# FireFly_AB.net
KiCad netlist of a schematic drawn in Altium Designer
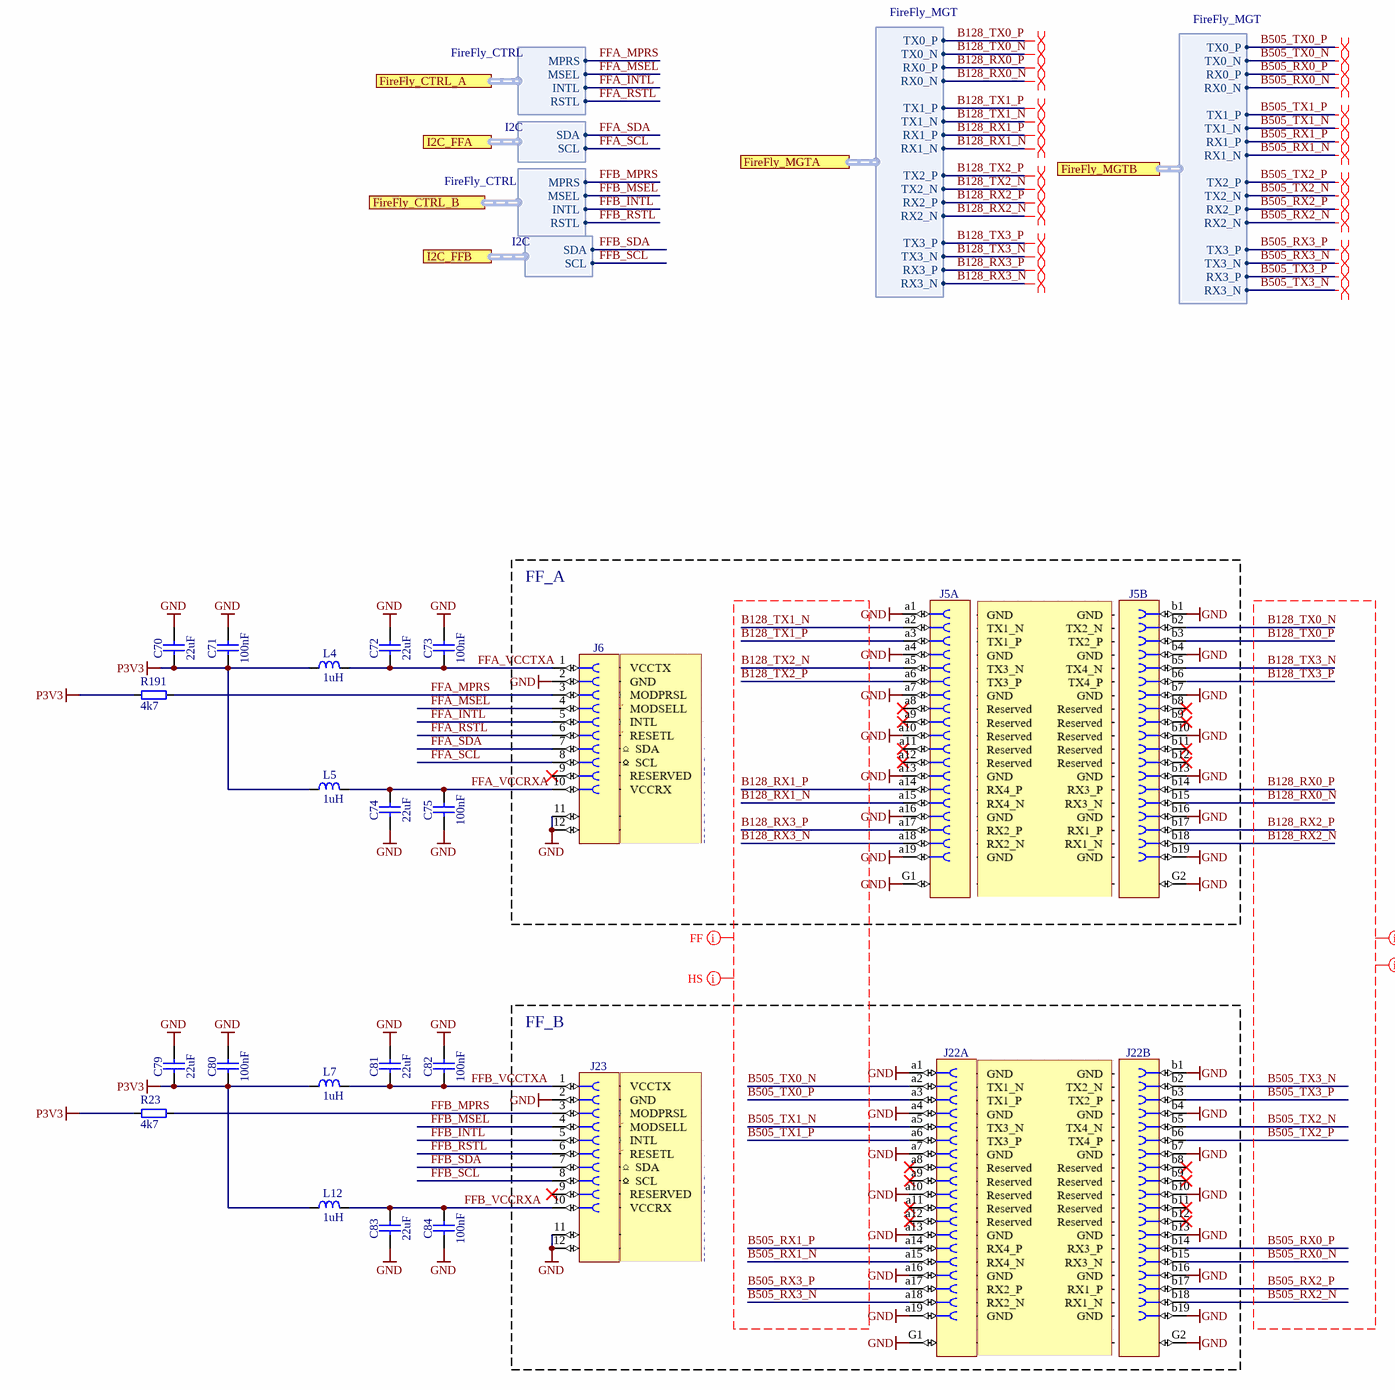
[diagram p0: FireFly_AB.SchDoc]

(export (version "E")
  (design (tool "Eeschema 10.0.6"))
  (components
    (comp (ref "C70")
      (value "22uF")
      (footprint "CAPC2012X135N")
      (description "Non-polarised capacitor")
      (fields
        (field (name "PART NUMBER") "CC0805_22UF_16V_10%_X5R")
        (field (name "VOLTAGE") "16V")
        (field (name "AUTHOR") "CERN DEM JLC")
      )
      (libsource (lib "Capacitors") (part "Capacitor - non polarized"))
    )
    (comp (ref "C71")
      (value "100nF")
      (footprint "CAPC1005X55N")
      (description "Non-polarised capacitor")
      (fields
        (field (name "PART NUMBER") "CC0402_100NF_16V_10%_X7R")
        (field (name "VOLTAGE") "16V")
        (field (name "AUTHOR") "CERN DEM JLC")
      )
      (libsource (lib "Capacitors") (part "Capacitor - non polarized"))
    )
    (comp (ref "C72")
      (value "22uF")
      (footprint "CAPC2012X135N")
      (description "Non-polarised capacitor")
      (fields
        (field (name "PART NUMBER") "CC0805_22UF_16V_10%_X5R")
        (field (name "VOLTAGE") "16V")
        (field (name "AUTHOR") "CERN DEM JLC")
      )
      (libsource (lib "Capacitors") (part "Capacitor - non polarized"))
    )
    (comp (ref "C73")
      (value "100nF")
      (footprint "CAPC1005X55N")
      (description "Non-polarised capacitor")
      (fields
        (field (name "PART NUMBER") "CC0402_100NF_16V_10%_X7R")
        (field (name "VOLTAGE") "16V")
        (field (name "AUTHOR") "CERN DEM JLC")
      )
      (libsource (lib "Capacitors") (part "Capacitor - non polarized"))
    )
    (comp (ref "C74")
      (value "22uF")
      (footprint "CAPC2012X135N")
      (description "Non-polarised capacitor")
      (fields
        (field (name "PART NUMBER") "CC0805_22UF_16V_10%_X5R")
        (field (name "VOLTAGE") "16V")
        (field (name "AUTHOR") "CERN DEM JLC")
      )
      (libsource (lib "Capacitors") (part "Capacitor - non polarized"))
    )
    (comp (ref "C75")
      (value "100nF")
      (footprint "CAPC1005X55N")
      (description "Non-polarised capacitor")
      (fields
        (field (name "PART NUMBER") "CC0402_100NF_16V_10%_X7R")
        (field (name "VOLTAGE") "16V")
        (field (name "AUTHOR") "CERN DEM JLC")
      )
      (libsource (lib "Capacitors") (part "Capacitor - non polarized"))
    )
    (comp (ref "C79")
      (value "22uF")
      (footprint "CAPC2012X135N")
      (description "Non-polarised capacitor")
      (fields
        (field (name "PART NUMBER") "CC0805_22UF_16V_10%_X5R")
        (field (name "VOLTAGE") "16V")
        (field (name "AUTHOR") "CERN DEM JLC")
      )
      (libsource (lib "Capacitors") (part "Capacitor - non polarized"))
    )
    (comp (ref "C80")
      (value "100nF")
      (footprint "CAPC1005X55N")
      (description "Non-polarised capacitor")
      (fields
        (field (name "PART NUMBER") "CC0402_100NF_16V_10%_X7R")
        (field (name "VOLTAGE") "16V")
        (field (name "AUTHOR") "CERN DEM JLC")
      )
      (libsource (lib "Capacitors") (part "Capacitor - non polarized"))
    )
    (comp (ref "C81")
      (value "22uF")
      (footprint "CAPC2012X135N")
      (description "Non-polarised capacitor")
      (fields
        (field (name "PART NUMBER") "CC0805_22UF_16V_10%_X5R")
        (field (name "VOLTAGE") "16V")
        (field (name "AUTHOR") "CERN DEM JLC")
      )
      (libsource (lib "Capacitors") (part "Capacitor - non polarized"))
    )
    (comp (ref "C82")
      (value "100nF")
      (footprint "CAPC1005X55N")
      (description "Non-polarised capacitor")
      (fields
        (field (name "PART NUMBER") "CC0402_100NF_16V_10%_X7R")
        (field (name "VOLTAGE") "16V")
        (field (name "AUTHOR") "CERN DEM JLC")
      )
      (libsource (lib "Capacitors") (part "Capacitor - non polarized"))
    )
    (comp (ref "C83")
      (value "22uF")
      (footprint "CAPC2012X135N")
      (description "Non-polarised capacitor")
      (fields
        (field (name "PART NUMBER") "CC0805_22UF_16V_10%_X5R")
        (field (name "VOLTAGE") "16V")
        (field (name "AUTHOR") "CERN DEM JLC")
      )
      (libsource (lib "Capacitors") (part "Capacitor - non polarized"))
    )
    (comp (ref "C84")
      (value "100nF")
      (footprint "CAPC1005X55N")
      (description "Non-polarised capacitor")
      (fields
        (field (name "PART NUMBER") "CC0402_100NF_16V_10%_X7R")
        (field (name "VOLTAGE") "16V")
        (field (name "AUTHOR") "CERN DEM JLC")
      )
      (libsource (lib "Capacitors") (part "Capacitor - non polarized"))
    )
    (comp (ref "J5")
      (value "Socket 38")
      (footprint "SAMTEC_UEC5-019-2-H-D-RA-1")
      (description "Connector 38ab Female (2x19) + 2x1")
      (fields
        (field (name "PART NUMBER") "SAMTEC_UEC5-019-2-H-D-RA-1")
        (field (name "MANUFACTURER") "SAMTEC")
        (field (name "AUTHOR") "CERN DEM BR")
      )
      (libsource (lib "") (part "Connector 38ab Female (2x19) + 2x1_1"))
    )
    (comp (ref "J6")
      (value "Socket 10")
      (footprint "SAMTEC_UCC8-010-1-H-S-1-A")
      (description "Connector 10 Female + 2")
      (fields
        (field (name "PART NUMBER") "SAMTEC_UCC8-010-1-H-S-1-A")
        (field (name "MANUFACTURER") "SAMTEC")
        (field (name "AUTHOR") "CERN DEM JLC")
      )
      (libsource (lib "Connectors") (part "Connector 10 Female + 2"))
    )
    (comp (ref "J22")
      (value "Socket 38")
      (footprint "SAMTEC_UEC5-019-2-H-D-RA-1")
      (description "Connector 38ab Female (2x19) + 2x1")
      (fields
        (field (name "PART NUMBER") "SAMTEC_UEC5-019-2-H-D-RA-1")
        (field (name "MANUFACTURER") "SAMTEC")
        (field (name "AUTHOR") "CERN DEM BR")
      )
      (libsource (lib "Connectors") (part "Connector 38ab Female (2x19) + 2x1"))
    )
    (comp (ref "J23")
      (value "Socket 10")
      (footprint "SAMTEC_UCC8-010-1-H-S-1-A")
      (description "Connector 10 Female + 2")
      (fields
        (field (name "PART NUMBER") "SAMTEC_UCC8-010-1-H-S-1-A")
        (field (name "MANUFACTURER") "SAMTEC")
        (field (name "AUTHOR") "CERN DEM JLC")
      )
      (libsource (lib "Connectors") (part "Connector 10 Female + 2"))
    )
    (comp (ref "L4")
      (value "1uH")
      (footprint "INDC2520X120N")
      (description "Inductor")
      (fields
        (field (name "TOLERANCE") "±20%")
        (field (name "PART NUMBER") "IND1008_1UH_20%_TDK_TFM252012ALVA1R0M")
        (field (name "AUTHOR") "CERN DEM BC")
      )
      (libsource (lib "Inductors & Transformers") (part "Inductor"))
    )
    (comp (ref "L5")
      (value "1uH")
      (footprint "INDC2520X120N")
      (description "Inductor")
      (fields
        (field (name "TOLERANCE") "±20%")
        (field (name "PART NUMBER") "IND1008_1UH_20%_TDK_TFM252012ALVA1R0M")
        (field (name "AUTHOR") "CERN DEM BC")
      )
      (libsource (lib "Inductors & Transformers") (part "Inductor"))
    )
    (comp (ref "L7")
      (value "1uH")
      (footprint "INDC2520X120N")
      (description "Inductor")
      (fields
        (field (name "TOLERANCE") "±20%")
        (field (name "PART NUMBER") "IND1008_1UH_20%_TDK_TFM252012ALVA1R0M")
        (field (name "AUTHOR") "CERN DEM BC")
      )
      (libsource (lib "Inductors & Transformers") (part "Inductor"))
    )
    (comp (ref "L12")
      (value "1uH")
      (footprint "INDC2520X120N")
      (description "Inductor")
      (fields
        (field (name "TOLERANCE") "±20%")
        (field (name "PART NUMBER") "IND1008_1UH_20%_TDK_TFM252012ALVA1R0M")
        (field (name "AUTHOR") "CERN DEM BC")
      )
      (libsource (lib "Inductors & Transformers") (part "Inductor"))
    )
    (comp (ref "R23")
      (value "4k7")
      (footprint "RESC1005X40N")
      (description "Resistor - 1%")
      (fields
        (field (name "TOLERANCE") "±1%")
        (field (name "PART NUMBER") "R0402_4K7_1%_0.0625W_100PPM")
        (field (name "AUTHOR") "CERN DEM JLC")
      )
      (libsource (lib "Resistors") (part "Resistor - 1%"))
    )
    (comp (ref "R191")
      (value "4k7")
      (footprint "RESC1005X40N")
      (description "Resistor - 1%")
      (fields
        (field (name "TOLERANCE") "±1%")
        (field (name "PART NUMBER") "R0402_4K7_1%_0.0625W_100PPM")
        (field (name "AUTHOR") "CERN DEM JLC")
      )
      (libsource (lib "Resistors") (part "Resistor - 1%"))
    )
  )
  (nets
    (net (code "4") (name "/B128_RX0_N") (class "Default")
      (node (ref "J5") (pin "b15") (pinfunction "15_b15") (pintype "bidirectional"))
    )
    (net (code "5") (name "/B128_RX0_P") (class "Default")
      (node (ref "J5") (pin "b14") (pinfunction "14_b14") (pintype "bidirectional"))
    )
    (net (code "6") (name "/B128_RX1_N") (class "Default")
      (node (ref "J5") (pin "a15") (pinfunction "15_a15") (pintype "bidirectional"))
    )
    (net (code "7") (name "/B128_RX1_P") (class "Default")
      (node (ref "J5") (pin "a14") (pinfunction "14_a14") (pintype "bidirectional"))
    )
    (net (code "8") (name "/B128_RX2_N") (class "Default")
      (node (ref "J5") (pin "b18") (pinfunction "18_b18") (pintype "bidirectional"))
    )
    (net (code "9") (name "/B128_RX2_P") (class "Default")
      (node (ref "J5") (pin "b17") (pinfunction "17_b17") (pintype "bidirectional"))
    )
    (net (code "10") (name "/B128_RX3_N") (class "Default")
      (node (ref "J5") (pin "a18") (pinfunction "18_a18") (pintype "bidirectional"))
    )
    (net (code "11") (name "/B128_RX3_P") (class "Default")
      (node (ref "J5") (pin "a17") (pinfunction "17_a17") (pintype "bidirectional"))
    )
    (net (code "12") (name "/B128_TX0_N") (class "Default")
      (node (ref "J5") (pin "b2") (pinfunction "2_b2") (pintype "bidirectional"))
    )
    (net (code "13") (name "/B128_TX0_P") (class "Default")
      (node (ref "J5") (pin "b3") (pinfunction "3_b3") (pintype "bidirectional"))
    )
    (net (code "14") (name "/B128_TX1_N") (class "Default")
      (node (ref "J5") (pin "a2") (pinfunction "2_a2") (pintype "bidirectional"))
    )
    (net (code "15") (name "/B128_TX1_P") (class "Default")
      (node (ref "J5") (pin "a3") (pinfunction "3_a3") (pintype "bidirectional"))
    )
    (net (code "16") (name "/B128_TX2_N") (class "Default")
      (node (ref "J5") (pin "a5") (pinfunction "5_a5") (pintype "bidirectional"))
    )
    (net (code "17") (name "/B128_TX2_P") (class "Default")
      (node (ref "J5") (pin "a6") (pinfunction "6_a6") (pintype "bidirectional"))
    )
    (net (code "18") (name "/B128_TX3_N") (class "Default")
      (node (ref "J5") (pin "b5") (pinfunction "5_b5") (pintype "bidirectional"))
    )
    (net (code "19") (name "/B128_TX3_P") (class "Default")
      (node (ref "J5") (pin "b6") (pinfunction "6_b6") (pintype "bidirectional"))
    )
    (net (code "20") (name "/B505_RX0_N") (class "Default")
      (node (ref "J22") (pin "b15") (pinfunction "15_b15") (pintype "bidirectional"))
    )
    (net (code "21") (name "/B505_RX0_P") (class "Default")
      (node (ref "J22") (pin "b14") (pinfunction "14_b14") (pintype "bidirectional"))
    )
    (net (code "22") (name "/B505_RX1_N") (class "Default")
      (node (ref "J22") (pin "a15") (pinfunction "15_a15") (pintype "bidirectional"))
    )
    (net (code "23") (name "/B505_RX1_P") (class "Default")
      (node (ref "J22") (pin "a14") (pinfunction "14_a14") (pintype "bidirectional"))
    )
    (net (code "24") (name "/B505_RX2_N") (class "Default")
      (node (ref "J22") (pin "b18") (pinfunction "18_b18") (pintype "bidirectional"))
    )
    (net (code "25") (name "/B505_RX2_P") (class "Default")
      (node (ref "J22") (pin "b17") (pinfunction "17_b17") (pintype "bidirectional"))
    )
    (net (code "26") (name "/B505_RX3_N") (class "Default")
      (node (ref "J22") (pin "a18") (pinfunction "18_a18") (pintype "bidirectional"))
    )
    (net (code "27") (name "/B505_RX3_P") (class "Default")
      (node (ref "J22") (pin "a17") (pinfunction "17_a17") (pintype "bidirectional"))
    )
    (net (code "28") (name "/B505_TX0_N") (class "Default")
      (node (ref "J22") (pin "a2") (pinfunction "2_a2") (pintype "bidirectional"))
    )
    (net (code "29") (name "/B505_TX0_P") (class "Default")
      (node (ref "J22") (pin "a3") (pinfunction "3_a3") (pintype "bidirectional"))
    )
    (net (code "30") (name "/B505_TX1_N") (class "Default")
      (node (ref "J22") (pin "a5") (pinfunction "5_a5") (pintype "bidirectional"))
    )
    (net (code "31") (name "/B505_TX1_P") (class "Default")
      (node (ref "J22") (pin "a6") (pinfunction "6_a6") (pintype "bidirectional"))
    )
    (net (code "32") (name "/B505_TX2_N") (class "Default")
      (node (ref "J22") (pin "b5") (pinfunction "5_b5") (pintype "bidirectional"))
    )
    (net (code "33") (name "/B505_TX2_P") (class "Default")
      (node (ref "J22") (pin "b6") (pinfunction "6_b6") (pintype "bidirectional"))
    )
    (net (code "34") (name "/B505_TX3_N") (class "Default")
      (node (ref "J22") (pin "b2") (pinfunction "2_b2") (pintype "bidirectional"))
    )
    (net (code "35") (name "/B505_TX3_P") (class "Default")
      (node (ref "J22") (pin "b3") (pinfunction "3_b3") (pintype "bidirectional"))
    )
    (net (code "36") (name "/FFA_INTL") (class "Default")
      (node (ref "J6") (pin "5") (pinfunction "5_5") (pintype "bidirectional"))
    )
    (net (code "37") (name "/FFA_MPRS") (class "Default")
      (node (ref "J6") (pin "3") (pinfunction "3_3") (pintype "bidirectional"))
      (node (ref "R191") (pin "2") (pinfunction "2_2") (pintype "passive"))
    )
    (net (code "38") (name "/FFA_MSEL") (class "Default")
      (node (ref "J6") (pin "4") (pinfunction "4_4") (pintype "bidirectional"))
    )
    (net (code "39") (name "/FFA_RSTL") (class "Default")
      (node (ref "J6") (pin "6") (pinfunction "6_6") (pintype "bidirectional"))
    )
    (net (code "40") (name "/FFA_SCL") (class "Default")
      (node (ref "J6") (pin "8") (pinfunction "8_8") (pintype "bidirectional"))
    )
    (net (code "41") (name "/FFA_SDA") (class "Default")
      (node (ref "J6") (pin "7") (pinfunction "7_7") (pintype "bidirectional"))
    )
    (net (code "42") (name "/FFA_VCCRXA") (class "Default")
      (node (ref "C74") (pin "2") (pinfunction "2_2") (pintype "passive"))
      (node (ref "C75") (pin "2") (pinfunction "2_2") (pintype "passive"))
      (node (ref "J6") (pin "10") (pinfunction "10_10") (pintype "bidirectional"))
      (node (ref "L5") (pin "2") (pinfunction "2_2") (pintype "passive"))
    )
    (net (code "43") (name "/FFA_VCCTXA") (class "Default")
      (node (ref "C72") (pin "1") (pinfunction "1_1") (pintype "passive"))
      (node (ref "C73") (pin "1") (pinfunction "1_1") (pintype "passive"))
      (node (ref "J6") (pin "1") (pinfunction "1_1") (pintype "bidirectional"))
      (node (ref "L4") (pin "2") (pinfunction "2_2") (pintype "passive"))
    )
    (net (code "44") (name "/FFB_INTL") (class "Default")
      (node (ref "J23") (pin "5") (pinfunction "5_5") (pintype "bidirectional"))
    )
    (net (code "45") (name "/FFB_MPRS") (class "Default")
      (node (ref "J23") (pin "3") (pinfunction "3_3") (pintype "bidirectional"))
      (node (ref "R23") (pin "2") (pinfunction "2_2") (pintype "passive"))
    )
    (net (code "46") (name "/FFB_MSEL") (class "Default")
      (node (ref "J23") (pin "4") (pinfunction "4_4") (pintype "bidirectional"))
    )
    (net (code "47") (name "/FFB_RSTL") (class "Default")
      (node (ref "J23") (pin "6") (pinfunction "6_6") (pintype "bidirectional"))
    )
    (net (code "48") (name "/FFB_SCL") (class "Default")
      (node (ref "J23") (pin "8") (pinfunction "8_8") (pintype "bidirectional"))
    )
    (net (code "49") (name "/FFB_SDA") (class "Default")
      (node (ref "J23") (pin "7") (pinfunction "7_7") (pintype "bidirectional"))
    )
    (net (code "50") (name "/FFB_VCCRXA") (class "Default")
      (node (ref "C83") (pin "2") (pinfunction "2_2") (pintype "passive"))
      (node (ref "C84") (pin "2") (pinfunction "2_2") (pintype "passive"))
      (node (ref "J23") (pin "10") (pinfunction "10_10") (pintype "bidirectional"))
      (node (ref "L12") (pin "2") (pinfunction "2_2") (pintype "passive"))
    )
    (net (code "51") (name "/FFB_VCCTXA") (class "Default")
      (node (ref "C81") (pin "1") (pinfunction "1_1") (pintype "passive"))
      (node (ref "C82") (pin "1") (pinfunction "1_1") (pintype "passive"))
      (node (ref "J23") (pin "1") (pinfunction "1_1") (pintype "bidirectional"))
      (node (ref "L7") (pin "2") (pinfunction "2_2") (pintype "passive"))
    )
    (net (code "55") (name "GND") (class "Default")
      (node (ref "C70") (pin "2") (pinfunction "2_2") (pintype "passive"))
      (node (ref "C71") (pin "2") (pinfunction "2_2") (pintype "passive"))
      (node (ref "C72") (pin "2") (pinfunction "2_2") (pintype "passive"))
      (node (ref "C73") (pin "2") (pinfunction "2_2") (pintype "passive"))
      (node (ref "C74") (pin "1") (pinfunction "1_1") (pintype "passive"))
      (node (ref "C75") (pin "1") (pinfunction "1_1") (pintype "passive"))
      (node (ref "C79") (pin "2") (pinfunction "2_2") (pintype "passive"))
      (node (ref "C80") (pin "2") (pinfunction "2_2") (pintype "passive"))
      (node (ref "C81") (pin "2") (pinfunction "2_2") (pintype "passive"))
      (node (ref "C82") (pin "2") (pinfunction "2_2") (pintype "passive"))
      (node (ref "C83") (pin "1") (pinfunction "1_1") (pintype "passive"))
      (node (ref "C84") (pin "1") (pinfunction "1_1") (pintype "passive"))
      (node (ref "J22") (pin "G1") (pinfunction "G1_G1") (pintype "bidirectional"))
      (node (ref "J22") (pin "G2") (pinfunction "G2_G2") (pintype "bidirectional"))
      (node (ref "J22") (pin "a1") (pinfunction "1_a1") (pintype "bidirectional"))
      (node (ref "J22") (pin "a10") (pinfunction "10_a10") (pintype "bidirectional"))
      (node (ref "J22") (pin "a13") (pinfunction "13_a13") (pintype "bidirectional"))
      (node (ref "J22") (pin "a16") (pinfunction "16_a16") (pintype "bidirectional"))
      (node (ref "J22") (pin "a19") (pinfunction "19_a19") (pintype "bidirectional"))
      (node (ref "J22") (pin "a4") (pinfunction "4_a4") (pintype "bidirectional"))
      (node (ref "J22") (pin "a7") (pinfunction "7_a7") (pintype "bidirectional"))
      (node (ref "J22") (pin "b1") (pinfunction "1_b1") (pintype "bidirectional"))
      (node (ref "J22") (pin "b10") (pinfunction "10_b10") (pintype "bidirectional"))
      (node (ref "J22") (pin "b13") (pinfunction "13_b13") (pintype "bidirectional"))
      (node (ref "J22") (pin "b16") (pinfunction "16_b16") (pintype "bidirectional"))
      (node (ref "J22") (pin "b19") (pinfunction "19_b19") (pintype "bidirectional"))
      (node (ref "J22") (pin "b4") (pinfunction "4_b4") (pintype "bidirectional"))
      (node (ref "J22") (pin "b7") (pinfunction "7_b7") (pintype "bidirectional"))
      (node (ref "J23") (pin "11") (pinfunction "11_11") (pintype "bidirectional"))
      (node (ref "J23") (pin "12") (pinfunction "12_12") (pintype "bidirectional"))
      (node (ref "J23") (pin "2") (pinfunction "2_2") (pintype "bidirectional"))
      (node (ref "J5") (pin "G1") (pinfunction "G1_G1") (pintype "bidirectional"))
      (node (ref "J5") (pin "G2") (pinfunction "G2_G2") (pintype "bidirectional"))
      (node (ref "J5") (pin "a1") (pinfunction "1_a1") (pintype "bidirectional"))
      (node (ref "J5") (pin "a10") (pinfunction "10_a10") (pintype "bidirectional"))
      (node (ref "J5") (pin "a13") (pinfunction "13_a13") (pintype "bidirectional"))
      (node (ref "J5") (pin "a16") (pinfunction "16_a16") (pintype "bidirectional"))
      (node (ref "J5") (pin "a19") (pinfunction "19_a19") (pintype "bidirectional"))
      (node (ref "J5") (pin "a4") (pinfunction "4_a4") (pintype "bidirectional"))
      (node (ref "J5") (pin "a7") (pinfunction "7_a7") (pintype "bidirectional"))
      (node (ref "J5") (pin "b1") (pinfunction "1_b1") (pintype "bidirectional"))
      (node (ref "J5") (pin "b10") (pinfunction "10_b10") (pintype "bidirectional"))
      (node (ref "J5") (pin "b13") (pinfunction "13_b13") (pintype "bidirectional"))
      (node (ref "J5") (pin "b16") (pinfunction "16_b16") (pintype "bidirectional"))
      (node (ref "J5") (pin "b19") (pinfunction "19_b19") (pintype "bidirectional"))
      (node (ref "J5") (pin "b4") (pinfunction "4_b4") (pintype "bidirectional"))
      (node (ref "J5") (pin "b7") (pinfunction "7_b7") (pintype "bidirectional"))
      (node (ref "J6") (pin "11") (pinfunction "11_11") (pintype "bidirectional"))
      (node (ref "J6") (pin "12") (pinfunction "12_12") (pintype "bidirectional"))
      (node (ref "J6") (pin "2") (pinfunction "2_2") (pintype "bidirectional"))
    )
    (net (code "56") (name "P3V3") (class "Default")
      (node (ref "C70") (pin "1") (pinfunction "1_1") (pintype "passive"))
      (node (ref "C71") (pin "1") (pinfunction "1_1") (pintype "passive"))
      (node (ref "C79") (pin "1") (pinfunction "1_1") (pintype "passive"))
      (node (ref "C80") (pin "1") (pinfunction "1_1") (pintype "passive"))
      (node (ref "L12") (pin "1") (pinfunction "1_1") (pintype "passive"))
      (node (ref "L4") (pin "1") (pinfunction "1_1") (pintype "passive"))
      (node (ref "L5") (pin "1") (pinfunction "1_1") (pintype "passive"))
      (node (ref "L7") (pin "1") (pinfunction "1_1") (pintype "passive"))
      (node (ref "R191") (pin "1") (pinfunction "1_1") (pintype "passive"))
      (node (ref "R23") (pin "1") (pinfunction "1_1") (pintype "passive"))
    )
    (net (code "57") (name "unconnected-(J5A-8-Pada8)") (class "Default")
      (node (ref "J5") (pin "a8") (pinfunction "8_a8") (pintype "bidirectional+no_connect"))
    )
    (net (code "58") (name "unconnected-(J5A-9-Pada9)") (class "Default")
      (node (ref "J5") (pin "a9") (pinfunction "9_a9") (pintype "bidirectional+no_connect"))
    )
    (net (code "59") (name "unconnected-(J5A-11-Pada11)") (class "Default")
      (node (ref "J5") (pin "a11") (pinfunction "11_a11") (pintype "bidirectional+no_connect"))
    )
    (net (code "60") (name "unconnected-(J5A-12-Pada12)") (class "Default")
      (node (ref "J5") (pin "a12") (pinfunction "12_a12") (pintype "bidirectional+no_connect"))
    )
    (net (code "61") (name "unconnected-(J5B-8-Padb8)") (class "Default")
      (node (ref "J5") (pin "b8") (pinfunction "8_b8") (pintype "bidirectional+no_connect"))
    )
    (net (code "62") (name "unconnected-(J5B-9-Padb9)") (class "Default")
      (node (ref "J5") (pin "b9") (pinfunction "9_b9") (pintype "bidirectional+no_connect"))
    )
    (net (code "63") (name "unconnected-(J5B-11-Padb11)") (class "Default")
      (node (ref "J5") (pin "b11") (pinfunction "11_b11") (pintype "bidirectional+no_connect"))
    )
    (net (code "64") (name "unconnected-(J5B-12-Padb12)") (class "Default")
      (node (ref "J5") (pin "b12") (pinfunction "12_b12") (pintype "bidirectional+no_connect"))
    )
    (net (code "65") (name "unconnected-(J6-Pad9)") (class "Default")
      (node (ref "J6") (pin "9") (pinfunction "9_9") (pintype "bidirectional+no_connect"))
    )
    (net (code "66") (name "unconnected-(J22A-8-Pada8)") (class "Default")
      (node (ref "J22") (pin "a8") (pinfunction "8_a8") (pintype "bidirectional+no_connect"))
    )
    (net (code "67") (name "unconnected-(J22A-9-Pada9)") (class "Default")
      (node (ref "J22") (pin "a9") (pinfunction "9_a9") (pintype "bidirectional+no_connect"))
    )
    (net (code "68") (name "unconnected-(J22A-11-Pada11)") (class "Default")
      (node (ref "J22") (pin "a11") (pinfunction "11_a11") (pintype "bidirectional+no_connect"))
    )
    (net (code "69") (name "unconnected-(J22A-12-Pada12)") (class "Default")
      (node (ref "J22") (pin "a12") (pinfunction "12_a12") (pintype "bidirectional+no_connect"))
    )
    (net (code "70") (name "unconnected-(J22B-8-Padb8)") (class "Default")
      (node (ref "J22") (pin "b8") (pinfunction "8_b8") (pintype "bidirectional+no_connect"))
    )
    (net (code "71") (name "unconnected-(J22B-9-Padb9)") (class "Default")
      (node (ref "J22") (pin "b9") (pinfunction "9_b9") (pintype "bidirectional+no_connect"))
    )
    (net (code "72") (name "unconnected-(J22B-11-Padb11)") (class "Default")
      (node (ref "J22") (pin "b11") (pinfunction "11_b11") (pintype "bidirectional+no_connect"))
    )
    (net (code "73") (name "unconnected-(J22B-12-Padb12)") (class "Default")
      (node (ref "J22") (pin "b12") (pinfunction "12_b12") (pintype "bidirectional+no_connect"))
    )
    (net (code "74") (name "unconnected-(J23-Pad9)") (class "Default")
      (node (ref "J23") (pin "9") (pinfunction "9_9") (pintype "bidirectional+no_connect"))
    )
  )
)
